# RF1_SSR8_HP_V4.net
KiCad netlist of a schematic drawn in EAGLE
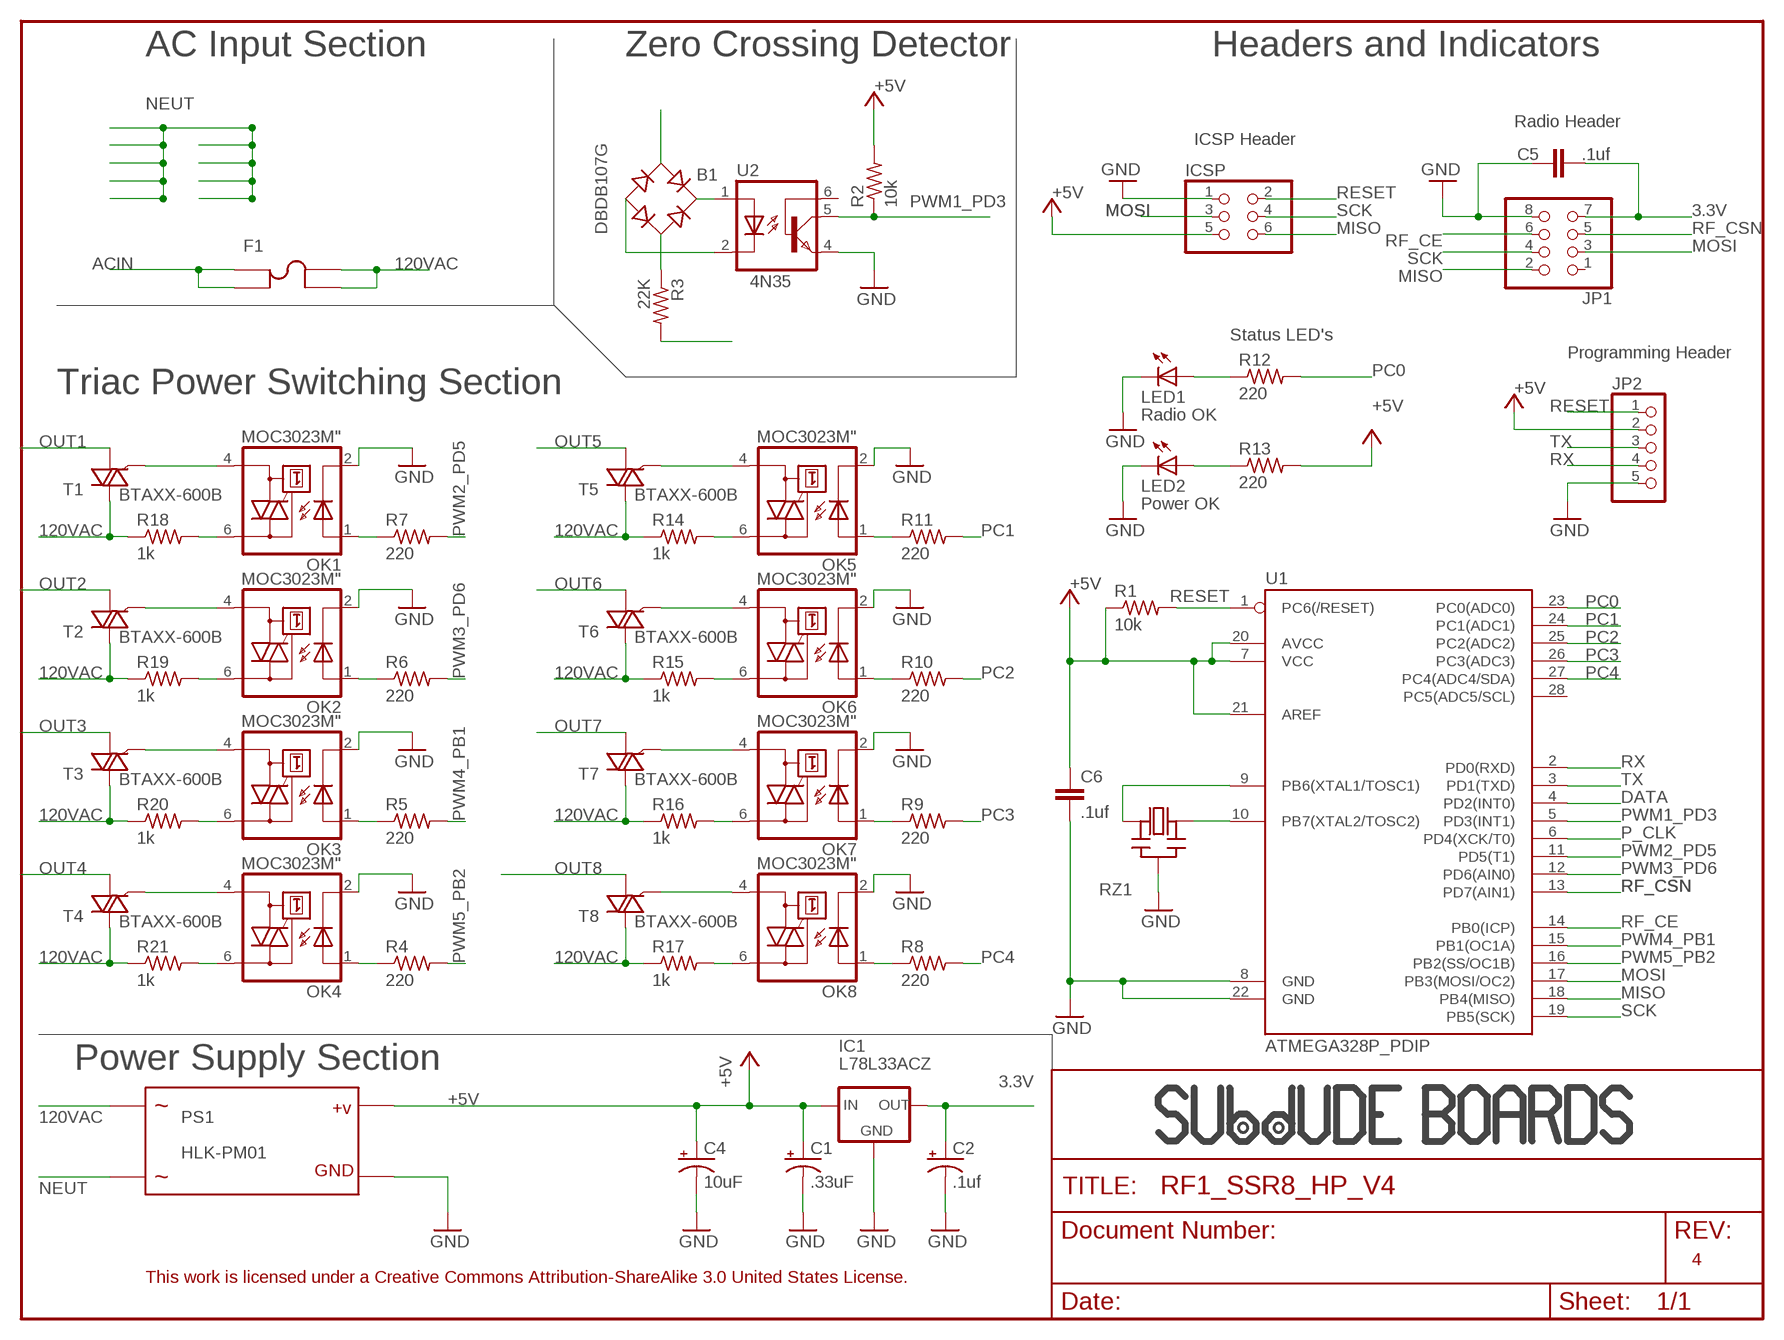
[diagram p0: schematic, sheet 1]

(export (version "E")
  (design (tool "Eeschema 10.0.6"))
  (components
    (comp (ref "B1")
      (value "DBDB107G")
      (footprint "eagle-import:DB")
      (libsource (lib "eagle-import") (part "DB?GDB107"))
    )
    (comp (ref "C1")
      (value ".33uF")
      (footprint "eagle-import:E1,8-4")
      (libsource (lib "eagle-import") (part "CPOL-USE1.8-4"))
    )
    (comp (ref "C2")
      (value ".1uf")
      (footprint "eagle-import:E1,8-4")
      (libsource (lib "eagle-import") (part "CPOL-USE1.8-4"))
    )
    (comp (ref "C4")
      (value "10uF")
      (footprint "eagle-import:E1,8-4")
      (libsource (lib "eagle-import") (part "CPOL-USE1.8-4"))
    )
    (comp (ref "C5")
      (value ".1uf")
      (footprint "eagle-import:C025-024X044")
      (libsource (lib "eagle-import") (part "C-EU025-024X044"))
    )
    (comp (ref "C6")
      (value ".1uf")
      (footprint "eagle-import:C025-024X044")
      (libsource (lib "eagle-import") (part "C-EU025-024X044"))
    )
    (comp (ref "F1")
      (value "FUSE5MMPCB")
      (footprint "eagle-import:KE3517")
      (libsource (lib "eagle-import") (part "FUSE5MMPCB"))
    )
    (comp (ref "IC1")
      (value "L78L33ACZ")
      (footprint "eagle-import:78LXX")
      (libsource (lib "eagle-import") (part "78LXX"))
    )
    (comp (ref "ICSP")
      (value "PINHD-2X3")
      (footprint "eagle-import:2X03")
      (libsource (lib "eagle-import") (part "PINHD-2X3"))
    )
    (comp (ref "JP1")
      (value "PINHD-2X4")
      (footprint "eagle-import:2X04")
      (libsource (lib "eagle-import") (part "PINHD-2X4"))
    )
    (comp (ref "JP2")
      (value "PINHD-1X51X05-BIG")
      (footprint "eagle-import:1X05-BIG")
      (libsource (lib "eagle-import") (part "PINHD-1X51X05-BIG"))
    )
    (comp (ref "LED1")
      (value "LED3MM")
      (footprint "eagle-import:LED3MM")
      (libsource (lib "eagle-import") (part "LED3MM"))
    )
    (comp (ref "LED2")
      (value "LED3MM")
      (footprint "eagle-import:LED3MM")
      (libsource (lib "eagle-import") (part "LED3MM"))
    )
    (comp (ref "OK1")
      (value "MOC3023M\"")
      (footprint "eagle-import:DIL06A")
      (libsource (lib "eagle-import") (part "MOC3023M{dblquote}"))
    )
    (comp (ref "OK2")
      (value "MOC3023M\"")
      (footprint "eagle-import:DIL06A")
      (libsource (lib "eagle-import") (part "MOC3023M{dblquote}"))
    )
    (comp (ref "OK3")
      (value "MOC3023M\"")
      (footprint "eagle-import:DIL06A")
      (libsource (lib "eagle-import") (part "MOC3023M{dblquote}"))
    )
    (comp (ref "OK4")
      (value "MOC3023M\"")
      (footprint "eagle-import:DIL06A")
      (libsource (lib "eagle-import") (part "MOC3023M{dblquote}"))
    )
    (comp (ref "OK5")
      (value "MOC3023M\"")
      (footprint "eagle-import:DIL06A")
      (libsource (lib "eagle-import") (part "MOC3023M{dblquote}"))
    )
    (comp (ref "OK6")
      (value "MOC3023M\"")
      (footprint "eagle-import:DIL06A")
      (libsource (lib "eagle-import") (part "MOC3023M{dblquote}"))
    )
    (comp (ref "OK7")
      (value "MOC3023M\"")
      (footprint "eagle-import:DIL06A")
      (libsource (lib "eagle-import") (part "MOC3023M{dblquote}"))
    )
    (comp (ref "OK8")
      (value "MOC3023M\"")
      (footprint "eagle-import:DIL06A")
      (libsource (lib "eagle-import") (part "MOC3023M{dblquote}"))
    )
    (comp (ref "PS1")
      (value "HLK-PM01")
      (footprint "eagle-import:HLK-PM01-STD")
      (libsource (lib "eagle-import") (part "HLK-PM01"))
    )
    (comp (ref "R1")
      (value "10k")
      (footprint "eagle-import:0207_7")
      (libsource (lib "eagle-import") (part "R-US_0207/7"))
    )
    (comp (ref "R2")
      (value "10k")
      (footprint "eagle-import:0207_2V")
      (libsource (lib "eagle-import") (part "resistor_R-US_0207/2V"))
    )
    (comp (ref "R3")
      (value "22K")
      (footprint "eagle-import:0411_12")
      (libsource (lib "eagle-import") (part "resistor_R-US_0411/12"))
    )
    (comp (ref "R4")
      (value "220")
      (footprint "eagle-import:0207_2V")
      (libsource (lib "eagle-import") (part "resistor_R-US_0207/2V"))
    )
    (comp (ref "R5")
      (value "220")
      (footprint "eagle-import:0207_2V")
      (libsource (lib "eagle-import") (part "resistor_R-US_0207/2V"))
    )
    (comp (ref "R6")
      (value "220")
      (footprint "eagle-import:0207_2V")
      (libsource (lib "eagle-import") (part "resistor_R-US_0207/2V"))
    )
    (comp (ref "R7")
      (value "220")
      (footprint "eagle-import:0207_2V")
      (libsource (lib "eagle-import") (part "resistor_R-US_0207/2V"))
    )
    (comp (ref "R8")
      (value "220")
      (footprint "eagle-import:0207_2V")
      (libsource (lib "eagle-import") (part "resistor_R-US_0207/2V"))
    )
    (comp (ref "R9")
      (value "220")
      (footprint "eagle-import:0207_2V")
      (libsource (lib "eagle-import") (part "resistor_R-US_0207/2V"))
    )
    (comp (ref "R10")
      (value "220")
      (footprint "eagle-import:0207_2V")
      (libsource (lib "eagle-import") (part "resistor_R-US_0207/2V"))
    )
    (comp (ref "R11")
      (value "220")
      (footprint "eagle-import:0207_2V")
      (libsource (lib "eagle-import") (part "resistor_R-US_0207/2V"))
    )
    (comp (ref "R12")
      (value "220")
      (footprint "eagle-import:0207_2V")
      (libsource (lib "eagle-import") (part "resistor_R-US_0207/2V"))
    )
    (comp (ref "R13")
      (value "220")
      (footprint "eagle-import:0207_2V")
      (libsource (lib "eagle-import") (part "resistor_R-US_0207/2V"))
    )
    (comp (ref "R14")
      (value "1k")
      (footprint "eagle-import:0207_2V")
      (libsource (lib "eagle-import") (part "resistor_R-US_0207/2V"))
    )
    (comp (ref "R15")
      (value "1k")
      (footprint "eagle-import:0207_2V")
      (libsource (lib "eagle-import") (part "resistor_R-US_0207/2V"))
    )
    (comp (ref "R16")
      (value "1k")
      (footprint "eagle-import:0207_2V")
      (libsource (lib "eagle-import") (part "resistor_R-US_0207/2V"))
    )
    (comp (ref "R17")
      (value "1k")
      (footprint "eagle-import:0207_2V")
      (libsource (lib "eagle-import") (part "resistor_R-US_0207/2V"))
    )
    (comp (ref "R18")
      (value "1k")
      (footprint "eagle-import:0207_2V")
      (libsource (lib "eagle-import") (part "resistor_R-US_0207/2V"))
    )
    (comp (ref "R19")
      (value "1k")
      (footprint "eagle-import:0207_2V")
      (libsource (lib "eagle-import") (part "resistor_R-US_0207/2V"))
    )
    (comp (ref "R20")
      (value "1k")
      (footprint "eagle-import:0207_2V")
      (libsource (lib "eagle-import") (part "resistor_R-US_0207/2V"))
    )
    (comp (ref "R21")
      (value "1k")
      (footprint "eagle-import:0207_2V")
      (libsource (lib "eagle-import") (part "resistor_R-US_0207/2V"))
    )
    (comp (ref "RZ1")
      (value "CERMOSCILL-THM")
      (footprint "eagle-import:CERM_OSC")
      (libsource (lib "eagle-import") (part "CERMOSCILL-THM"))
    )
    (comp (ref "T1")
      (value "BTAXX-600B")
      (footprint "eagle-import:TO220BVA")
      (libsource (lib "eagle-import") (part "BTAXX-600B"))
    )
    (comp (ref "T2")
      (value "BTAXX-600B")
      (footprint "eagle-import:TO220BVA")
      (libsource (lib "eagle-import") (part "BTAXX-600B"))
    )
    (comp (ref "T3")
      (value "BTAXX-600B")
      (footprint "eagle-import:TO220BVA")
      (libsource (lib "eagle-import") (part "BTAXX-600B"))
    )
    (comp (ref "T4")
      (value "BTAXX-600B")
      (footprint "eagle-import:TO220BVA")
      (libsource (lib "eagle-import") (part "BTAXX-600B"))
    )
    (comp (ref "T5")
      (value "BTAXX-600B")
      (footprint "eagle-import:TO220BVA")
      (libsource (lib "eagle-import") (part "BTAXX-600B"))
    )
    (comp (ref "T6")
      (value "BTAXX-600B")
      (footprint "eagle-import:TO220BVA")
      (libsource (lib "eagle-import") (part "BTAXX-600B"))
    )
    (comp (ref "T7")
      (value "BTAXX-600B")
      (footprint "eagle-import:TO220BVA")
      (libsource (lib "eagle-import") (part "BTAXX-600B"))
    )
    (comp (ref "T8")
      (value "BTAXX-600B")
      (footprint "eagle-import:TO220BVA")
      (libsource (lib "eagle-import") (part "BTAXX-600B"))
    )
    (comp (ref "U$2")
      (value "SUBDUDE_LOGOLARGE")
      (footprint "eagle-import:SUBDUDE_LARGE")
      (libsource (lib "eagle-import") (part "SUBDUDE_LOGOLARGE"))
    )
    (comp (ref "U$3")
      (value "SUBDUDE_LOGOSMALL")
      (footprint "eagle-import:SUBDUDE_SMALL")
      (libsource (lib "eagle-import") (part "SUBDUDE_LOGOSMALL"))
    )
    (comp (ref "U1")
      (value "ATMEGA328P_PDIP")
      (footprint "eagle-import:DIL28-3")
      (libsource (lib "eagle-import") (part "ATMEGA328P_PDIP"))
    )
    (comp (ref "U2")
      (value "4N35SMALL")
      (footprint "eagle-import:DIL06A")
      (libsource (lib "eagle-import") (part "4N35SMALL"))
    )
  )
  (nets
    (net (code "1") (name "+5V") (class "Default")
      (node (ref "C1") (pin "+") (pinfunction "+_+") (pintype "passive"))
      (node (ref "C4") (pin "+") (pinfunction "+_+") (pintype "passive"))
      (node (ref "C6") (pin "1") (pinfunction "1_1") (pintype "passive"))
      (node (ref "IC1") (pin "IN") (pinfunction "IN_IN") (pintype "input"))
      (node (ref "ICSP") (pin "5") (pinfunction "5_5") (pintype "passive"))
      (node (ref "JP2") (pin "2") (pinfunction "2_2") (pintype "passive"))
      (node (ref "PS1") (pin "VO+") (pinfunction "P$3_VO+") (pintype "bidirectional"))
      (node (ref "R1") (pin "1") (pinfunction "1_1") (pintype "passive"))
      (node (ref "R13") (pin "2") (pinfunction "2_2") (pintype "passive"))
      (node (ref "R2") (pin "2") (pinfunction "2_2") (pintype "passive"))
      (node (ref "U1") (pin "20") (pinfunction "AVCC_20") (pintype "bidirectional"))
      (node (ref "U1") (pin "21") (pinfunction "AREF_21") (pintype "bidirectional"))
      (node (ref "U1") (pin "7") (pinfunction "VCC_7") (pintype "bidirectional"))
    )
    (net (code "2") (name "/3.3V") (class "Default")
      (node (ref "C2") (pin "+") (pinfunction "+_+") (pintype "passive"))
      (node (ref "C5") (pin "2") (pinfunction "2_2") (pintype "passive"))
      (node (ref "IC1") (pin "OUT") (pinfunction "OUT_OUT") (pintype "passive"))
      (node (ref "JP1") (pin "7") (pinfunction "7_7") (pintype "passive"))
    )
    (net (code "3") (name "/120VAC") (class "Default")
      (node (ref "F1") (pin "P$2") (pinfunction "P$2_P$2") (pintype "bidirectional"))
      (node (ref "F1") (pin "P$4") (pinfunction "P$4_P$4") (pintype "bidirectional"))
      (node (ref "PS1") (pin "AC_N") (pinfunction "P$1_AC_N") (pintype "bidirectional"))
      (node (ref "R14") (pin "1") (pinfunction "1_1") (pintype "passive"))
      (node (ref "R15") (pin "1") (pinfunction "1_1") (pintype "passive"))
      (node (ref "R16") (pin "1") (pinfunction "1_1") (pintype "passive"))
      (node (ref "R17") (pin "1") (pinfunction "1_1") (pintype "passive"))
      (node (ref "R18") (pin "1") (pinfunction "1_1") (pintype "passive"))
      (node (ref "R19") (pin "1") (pinfunction "1_1") (pintype "passive"))
      (node (ref "R20") (pin "1") (pinfunction "1_1") (pintype "passive"))
      (node (ref "R21") (pin "1") (pinfunction "1_1") (pintype "passive"))
      (node (ref "R3") (pin "2") (pinfunction "2_2") (pintype "passive"))
      (node (ref "T1") (pin "T2") (pinfunction "A2_T2") (pintype "passive"))
      (node (ref "T2") (pin "T2") (pinfunction "A2_T2") (pintype "passive"))
      (node (ref "T3") (pin "T2") (pinfunction "A2_T2") (pintype "passive"))
      (node (ref "T4") (pin "T2") (pinfunction "A2_T2") (pintype "passive"))
      (node (ref "T5") (pin "T2") (pinfunction "A2_T2") (pintype "passive"))
      (node (ref "T6") (pin "T2") (pinfunction "A2_T2") (pintype "passive"))
      (node (ref "T7") (pin "T2") (pinfunction "A2_T2") (pintype "passive"))
      (node (ref "T8") (pin "T2") (pinfunction "A2_T2") (pintype "passive"))
    )
    (net (code "4") (name "/ACIN") (class "Default")
      (node (ref "F1") (pin "P$1") (pinfunction "P$1_P$1") (pintype "bidirectional"))
      (node (ref "F1") (pin "P$3") (pinfunction "P$3_P$3") (pintype "bidirectional"))
    )
    (net (code "5") (name "/DATA") (class "Default")
      (node (ref "U1") (pin "4") (pinfunction "PD2(INT0)_4") (pintype "bidirectional"))
    )
    (net (code "6") (name "/MISO") (class "Default")
      (node (ref "ICSP") (pin "6") (pinfunction "6_6") (pintype "passive"))
      (node (ref "JP1") (pin "2") (pinfunction "2_2") (pintype "passive"))
      (node (ref "U1") (pin "18") (pinfunction "PB4(MISO)_18") (pintype "bidirectional"))
    )
    (net (code "7") (name "/MOSI") (class "Default")
      (node (ref "ICSP") (pin "3") (pinfunction "3_3") (pintype "passive"))
      (node (ref "JP1") (pin "3") (pinfunction "3_3") (pintype "passive"))
      (node (ref "U1") (pin "17") (pinfunction "PB3(MOSI/OC2)_17") (pintype "bidirectional"))
    )
    (net (code "8") (name "/NEUT") (class "Default")
      (node (ref "B1") (pin "AC1") (pinfunction "AC1_AC1") (pintype "passive"))
      (node (ref "PS1") (pin "AC_L") (pinfunction "P$2_AC_L") (pintype "bidirectional"))
    )
    (net (code "9") (name "/OUT1") (class "Default")
      (node (ref "T1") (pin "T1") (pinfunction "A1_T1") (pintype "passive"))
    )
    (net (code "10") (name "/OUT2") (class "Default")
      (node (ref "T2") (pin "T1") (pinfunction "A1_T1") (pintype "passive"))
    )
    (net (code "11") (name "/OUT3") (class "Default")
      (node (ref "T3") (pin "T1") (pinfunction "A1_T1") (pintype "passive"))
    )
    (net (code "12") (name "/OUT4") (class "Default")
      (node (ref "T4") (pin "T1") (pinfunction "A1_T1") (pintype "passive"))
    )
    (net (code "13") (name "/OUT5") (class "Default")
      (node (ref "T5") (pin "T1") (pinfunction "A1_T1") (pintype "passive"))
    )
    (net (code "14") (name "/OUT6") (class "Default")
      (node (ref "T6") (pin "T1") (pinfunction "A1_T1") (pintype "passive"))
    )
    (net (code "15") (name "/OUT7") (class "Default")
      (node (ref "T7") (pin "T1") (pinfunction "A1_T1") (pintype "passive"))
    )
    (net (code "16") (name "/OUT8") (class "Default")
      (node (ref "T8") (pin "T1") (pinfunction "A1_T1") (pintype "passive"))
    )
    (net (code "17") (name "/PC0") (class "Default")
      (node (ref "R12") (pin "2") (pinfunction "2_2") (pintype "passive"))
      (node (ref "U1") (pin "23") (pinfunction "PC0(ADC0)_23") (pintype "bidirectional"))
    )
    (net (code "18") (name "/PC1") (class "Default")
      (node (ref "R11") (pin "2") (pinfunction "2_2") (pintype "passive"))
      (node (ref "U1") (pin "24") (pinfunction "PC1(ADC1)_24") (pintype "bidirectional"))
    )
    (net (code "19") (name "/PC2") (class "Default")
      (node (ref "R10") (pin "2") (pinfunction "2_2") (pintype "passive"))
      (node (ref "U1") (pin "25") (pinfunction "PC2(ADC2)_25") (pintype "bidirectional"))
    )
    (net (code "20") (name "/PC3") (class "Default")
      (node (ref "R9") (pin "2") (pinfunction "2_2") (pintype "passive"))
      (node (ref "U1") (pin "26") (pinfunction "PC3(ADC3)_26") (pintype "bidirectional"))
    )
    (net (code "21") (name "/PC4") (class "Default")
      (node (ref "R8") (pin "2") (pinfunction "2_2") (pintype "passive"))
      (node (ref "U1") (pin "27") (pinfunction "PC4(ADC4/SDA)_27") (pintype "bidirectional"))
    )
    (net (code "22") (name "/PWM1_PD3") (class "Default")
      (node (ref "R2") (pin "1") (pinfunction "1_1") (pintype "passive"))
      (node (ref "U1") (pin "5") (pinfunction "PD3(INT1)_5") (pintype "bidirectional"))
      (node (ref "U2") (pin "5") (pinfunction "COL_5") (pintype "passive"))
    )
    (net (code "23") (name "/PWM2_PD5") (class "Default")
      (node (ref "R7") (pin "2") (pinfunction "2_2") (pintype "passive"))
      (node (ref "U1") (pin "11") (pinfunction "PD5(T1)_11") (pintype "bidirectional"))
    )
    (net (code "24") (name "/PWM3_PD6") (class "Default")
      (node (ref "R6") (pin "2") (pinfunction "2_2") (pintype "passive"))
      (node (ref "U1") (pin "12") (pinfunction "PD6(AIN0)_12") (pintype "bidirectional"))
    )
    (net (code "25") (name "/PWM4_PB1") (class "Default")
      (node (ref "R5") (pin "2") (pinfunction "2_2") (pintype "passive"))
      (node (ref "U1") (pin "15") (pinfunction "PB1(OC1A)_15") (pintype "bidirectional"))
    )
    (net (code "26") (name "/PWM5_PB2") (class "Default")
      (node (ref "R4") (pin "2") (pinfunction "2_2") (pintype "passive"))
      (node (ref "U1") (pin "16") (pinfunction "PB2(SS/OC1B)_16") (pintype "bidirectional"))
    )
    (net (code "27") (name "/P_CLK") (class "Default")
      (node (ref "U1") (pin "6") (pinfunction "PD4(XCK/T0)_6") (pintype "bidirectional"))
    )
    (net (code "28") (name "/RESET") (class "Default")
      (node (ref "ICSP") (pin "2") (pinfunction "2_2") (pintype "passive"))
      (node (ref "JP2") (pin "1") (pinfunction "1_1") (pintype "passive"))
      (node (ref "R1") (pin "2") (pinfunction "2_2") (pintype "passive"))
      (node (ref "U1") (pin "1") (pinfunction "PC6(/RESET)_1") (pintype "bidirectional"))
    )
    (net (code "29") (name "/RF_CE") (class "Default")
      (node (ref "JP1") (pin "6") (pinfunction "6_6") (pintype "passive"))
      (node (ref "U1") (pin "14") (pinfunction "PB0(ICP)_14") (pintype "bidirectional"))
    )
    (net (code "30") (name "/RF_CSN") (class "Default")
      (node (ref "JP1") (pin "5") (pinfunction "5_5") (pintype "passive"))
      (node (ref "U1") (pin "13") (pinfunction "PD7(AIN1)_13") (pintype "bidirectional"))
    )
    (net (code "31") (name "/RX") (class "Default")
      (node (ref "JP2") (pin "4") (pinfunction "4_4") (pintype "passive"))
      (node (ref "U1") (pin "2") (pinfunction "PD0(RXD)_2") (pintype "bidirectional"))
    )
    (net (code "32") (name "/SCK") (class "Default")
      (node (ref "ICSP") (pin "4") (pinfunction "4_4") (pintype "passive"))
      (node (ref "JP1") (pin "4") (pinfunction "4_4") (pintype "passive"))
      (node (ref "U1") (pin "19") (pinfunction "PB5(SCK)_19") (pintype "bidirectional"))
    )
    (net (code "33") (name "/TX") (class "Default")
      (node (ref "JP2") (pin "3") (pinfunction "3_3") (pintype "passive"))
      (node (ref "U1") (pin "3") (pinfunction "PD1(TXD)_3") (pintype "bidirectional"))
    )
    (net (code "34") (name "GND") (class "Default")
      (node (ref "C1") (pin "-") (pinfunction "-_-") (pintype "passive"))
      (node (ref "C2") (pin "-") (pinfunction "-_-") (pintype "passive"))
      (node (ref "C4") (pin "-") (pinfunction "-_-") (pintype "passive"))
      (node (ref "C5") (pin "1") (pinfunction "1_1") (pintype "passive"))
      (node (ref "C6") (pin "2") (pinfunction "2_2") (pintype "passive"))
      (node (ref "IC1") (pin "GND") (pinfunction "GND_GND") (pintype "input"))
      (node (ref "ICSP") (pin "1") (pinfunction "1_1") (pintype "passive"))
      (node (ref "JP1") (pin "8") (pinfunction "8_8") (pintype "passive"))
      (node (ref "JP2") (pin "5") (pinfunction "5_5") (pintype "passive"))
      (node (ref "LED1") (pin "K") (pinfunction "C_K") (pintype "passive"))
      (node (ref "LED2") (pin "K") (pinfunction "C_K") (pintype "passive"))
      (node (ref "OK1") (pin "2") (pinfunction "C_2") (pintype "passive"))
      (node (ref "OK2") (pin "2") (pinfunction "C_2") (pintype "passive"))
      (node (ref "OK3") (pin "2") (pinfunction "C_2") (pintype "passive"))
      (node (ref "OK4") (pin "2") (pinfunction "C_2") (pintype "passive"))
      (node (ref "OK5") (pin "2") (pinfunction "C_2") (pintype "passive"))
      (node (ref "OK6") (pin "2") (pinfunction "C_2") (pintype "passive"))
      (node (ref "OK7") (pin "2") (pinfunction "C_2") (pintype "passive"))
      (node (ref "OK8") (pin "2") (pinfunction "C_2") (pintype "passive"))
      (node (ref "PS1") (pin "VO-") (pinfunction "P$4_VO-") (pintype "bidirectional"))
      (node (ref "RZ1") (pin "P$2") (pinfunction "GND_P$2") (pintype "bidirectional"))
      (node (ref "U1") (pin "22") (pinfunction "GND_22") (pintype "bidirectional"))
      (node (ref "U1") (pin "8") (pinfunction "GND_8") (pintype "bidirectional"))
      (node (ref "U2") (pin "4") (pinfunction "EMI_4") (pintype "passive"))
    )
    (net (code "35") (name "Net-(B1-PadAC2)") (class "Default")
      (node (ref "B1") (pin "AC2") (pinfunction "AC2_AC2") (pintype "passive"))
      (node (ref "R3") (pin "1") (pinfunction "1_1") (pintype "passive"))
    )
    (net (code "36") (name "Net-(LED1-PadA)") (class "Default")
      (node (ref "LED1") (pin "A") (pinfunction "A_A") (pintype "passive"))
      (node (ref "R12") (pin "1") (pinfunction "1_1") (pintype "passive"))
    )
    (net (code "37") (name "Net-(LED2-PadA)") (class "Default")
      (node (ref "LED2") (pin "A") (pinfunction "A_A") (pintype "passive"))
      (node (ref "R13") (pin "1") (pinfunction "1_1") (pintype "passive"))
    )
    (net (code "38") (name "Net-(OK1-A)") (class "Default")
      (node (ref "OK1") (pin "1") (pinfunction "A_1") (pintype "passive"))
      (node (ref "R7") (pin "1") (pinfunction "1_1") (pintype "passive"))
    )
    (net (code "39") (name "Net-(OK1-A1)") (class "Default")
      (node (ref "OK1") (pin "4") (pinfunction "A1_4") (pintype "passive"))
      (node (ref "T1") (pin "G") (pinfunction "G_G") (pintype "passive"))
    )
    (net (code "40") (name "Net-(OK1-A2)") (class "Default")
      (node (ref "OK1") (pin "6") (pinfunction "A2_6") (pintype "passive"))
      (node (ref "R18") (pin "2") (pinfunction "2_2") (pintype "passive"))
    )
    (net (code "41") (name "Net-(OK2-A)") (class "Default")
      (node (ref "OK2") (pin "1") (pinfunction "A_1") (pintype "passive"))
      (node (ref "R6") (pin "1") (pinfunction "1_1") (pintype "passive"))
    )
    (net (code "42") (name "Net-(OK2-A1)") (class "Default")
      (node (ref "OK2") (pin "4") (pinfunction "A1_4") (pintype "passive"))
      (node (ref "T2") (pin "G") (pinfunction "G_G") (pintype "passive"))
    )
    (net (code "43") (name "Net-(OK2-A2)") (class "Default")
      (node (ref "OK2") (pin "6") (pinfunction "A2_6") (pintype "passive"))
      (node (ref "R19") (pin "2") (pinfunction "2_2") (pintype "passive"))
    )
    (net (code "44") (name "Net-(OK3-A)") (class "Default")
      (node (ref "OK3") (pin "1") (pinfunction "A_1") (pintype "passive"))
      (node (ref "R5") (pin "1") (pinfunction "1_1") (pintype "passive"))
    )
    (net (code "45") (name "Net-(OK3-A1)") (class "Default")
      (node (ref "OK3") (pin "4") (pinfunction "A1_4") (pintype "passive"))
      (node (ref "T3") (pin "G") (pinfunction "G_G") (pintype "passive"))
    )
    (net (code "46") (name "Net-(OK3-A2)") (class "Default")
      (node (ref "OK3") (pin "6") (pinfunction "A2_6") (pintype "passive"))
      (node (ref "R20") (pin "2") (pinfunction "2_2") (pintype "passive"))
    )
    (net (code "47") (name "Net-(OK4-A)") (class "Default")
      (node (ref "OK4") (pin "1") (pinfunction "A_1") (pintype "passive"))
      (node (ref "R4") (pin "1") (pinfunction "1_1") (pintype "passive"))
    )
    (net (code "48") (name "Net-(OK4-A1)") (class "Default")
      (node (ref "OK4") (pin "4") (pinfunction "A1_4") (pintype "passive"))
      (node (ref "T4") (pin "G") (pinfunction "G_G") (pintype "passive"))
    )
    (net (code "49") (name "Net-(OK4-A2)") (class "Default")
      (node (ref "OK4") (pin "6") (pinfunction "A2_6") (pintype "passive"))
      (node (ref "R21") (pin "2") (pinfunction "2_2") (pintype "passive"))
    )
    (net (code "50") (name "Net-(OK5-A)") (class "Default")
      (node (ref "OK5") (pin "1") (pinfunction "A_1") (pintype "passive"))
      (node (ref "R11") (pin "1") (pinfunction "1_1") (pintype "passive"))
    )
    (net (code "51") (name "Net-(OK5-A1)") (class "Default")
      (node (ref "OK5") (pin "4") (pinfunction "A1_4") (pintype "passive"))
      (node (ref "T5") (pin "G") (pinfunction "G_G") (pintype "passive"))
    )
    (net (code "52") (name "Net-(OK5-A2)") (class "Default")
      (node (ref "OK5") (pin "6") (pinfunction "A2_6") (pintype "passive"))
      (node (ref "R14") (pin "2") (pinfunction "2_2") (pintype "passive"))
    )
    (net (code "53") (name "Net-(OK6-A)") (class "Default")
      (node (ref "OK6") (pin "1") (pinfunction "A_1") (pintype "passive"))
      (node (ref "R10") (pin "1") (pinfunction "1_1") (pintype "passive"))
    )
    (net (code "54") (name "Net-(OK6-A1)") (class "Default")
      (node (ref "OK6") (pin "4") (pinfunction "A1_4") (pintype "passive"))
      (node (ref "T6") (pin "G") (pinfunction "G_G") (pintype "passive"))
    )
    (net (code "55") (name "Net-(OK6-A2)") (class "Default")
      (node (ref "OK6") (pin "6") (pinfunction "A2_6") (pintype "passive"))
      (node (ref "R15") (pin "2") (pinfunction "2_2") (pintype "passive"))
    )
    (net (code "56") (name "Net-(OK7-A)") (class "Default")
      (node (ref "OK7") (pin "1") (pinfunction "A_1") (pintype "passive"))
      (node (ref "R9") (pin "1") (pinfunction "1_1") (pintype "passive"))
    )
    (net (code "57") (name "Net-(OK7-A1)") (class "Default")
      (node (ref "OK7") (pin "4") (pinfunction "A1_4") (pintype "passive"))
      (node (ref "T7") (pin "G") (pinfunction "G_G") (pintype "passive"))
    )
    (net (code "58") (name "Net-(OK7-A2)") (class "Default")
      (node (ref "OK7") (pin "6") (pinfunction "A2_6") (pintype "passive"))
      (node (ref "R16") (pin "2") (pinfunction "2_2") (pintype "passive"))
    )
    (net (code "59") (name "Net-(OK8-A)") (class "Default")
      (node (ref "OK8") (pin "1") (pinfunction "A_1") (pintype "passive"))
      (node (ref "R8") (pin "1") (pinfunction "1_1") (pintype "passive"))
    )
    (net (code "60") (name "Net-(OK8-A1)") (class "Default")
      (node (ref "OK8") (pin "4") (pinfunction "A1_4") (pintype "passive"))
      (node (ref "T8") (pin "G") (pinfunction "G_G") (pintype "passive"))
    )
    (net (code "61") (name "Net-(OK8-A2)") (class "Default")
      (node (ref "OK8") (pin "6") (pinfunction "A2_6") (pintype "passive"))
      (node (ref "R17") (pin "2") (pinfunction "2_2") (pintype "passive"))
    )
    (net (code "62") (name "Net-(RZ1-IN)") (class "Default")
      (node (ref "RZ1") (pin "P$1") (pinfunction "IN_P$1") (pintype "bidirectional"))
      (node (ref "U1") (pin "9") (pinfunction "PB6(XTAL1/TOSC1)_9") (pintype "bidirectional"))
    )
    (net (code "63") (name "Net-(RZ1-OUT)") (class "Default")
      (node (ref "RZ1") (pin "P$3") (pinfunction "OUT_P$3") (pintype "bidirectional"))
      (node (ref "U1") (pin "10") (pinfunction "PB7(XTAL2/TOSC2)_10") (pintype "bidirectional"))
    )
    (net (code "64") (name "Net-(U2-A)") (class "Default")
      (node (ref "B1") (pin "+") (pinfunction "+_+") (pintype "passive"))
      (node (ref "U2") (pin "1") (pinfunction "A_1") (pintype "passive"))
    )
    (net (code "65") (name "Net-(U2-C)") (class "Default")
      (node (ref "B1") (pin "-") (pinfunction "-_-") (pintype "passive"))
      (node (ref "U2") (pin "2") (pinfunction "C_2") (pintype "passive"))
    )
    (net (code "66") (name "unconnected-(JP1-Pad1)") (class "Default")
      (node (ref "JP1") (pin "1") (pinfunction "1_1") (pintype "passive"))
    )
    (net (code "67") (name "unconnected-(U1-PC5(ADC5{slash}SCL)-Pad28)") (class "Default")
      (node (ref "U1") (pin "28") (pinfunction "PC5(ADC5/SCL)_28") (pintype "bidirectional"))
    )
    (net (code "68") (name "unconnected-(U2-BAS-Pad6)") (class "Default")
      (node (ref "U2") (pin "6") (pinfunction "BAS_6") (pintype "passive"))
    )
  )
)
